# openx3_rev2.net
KiCad netlist of a schematic drawn in EAGLE
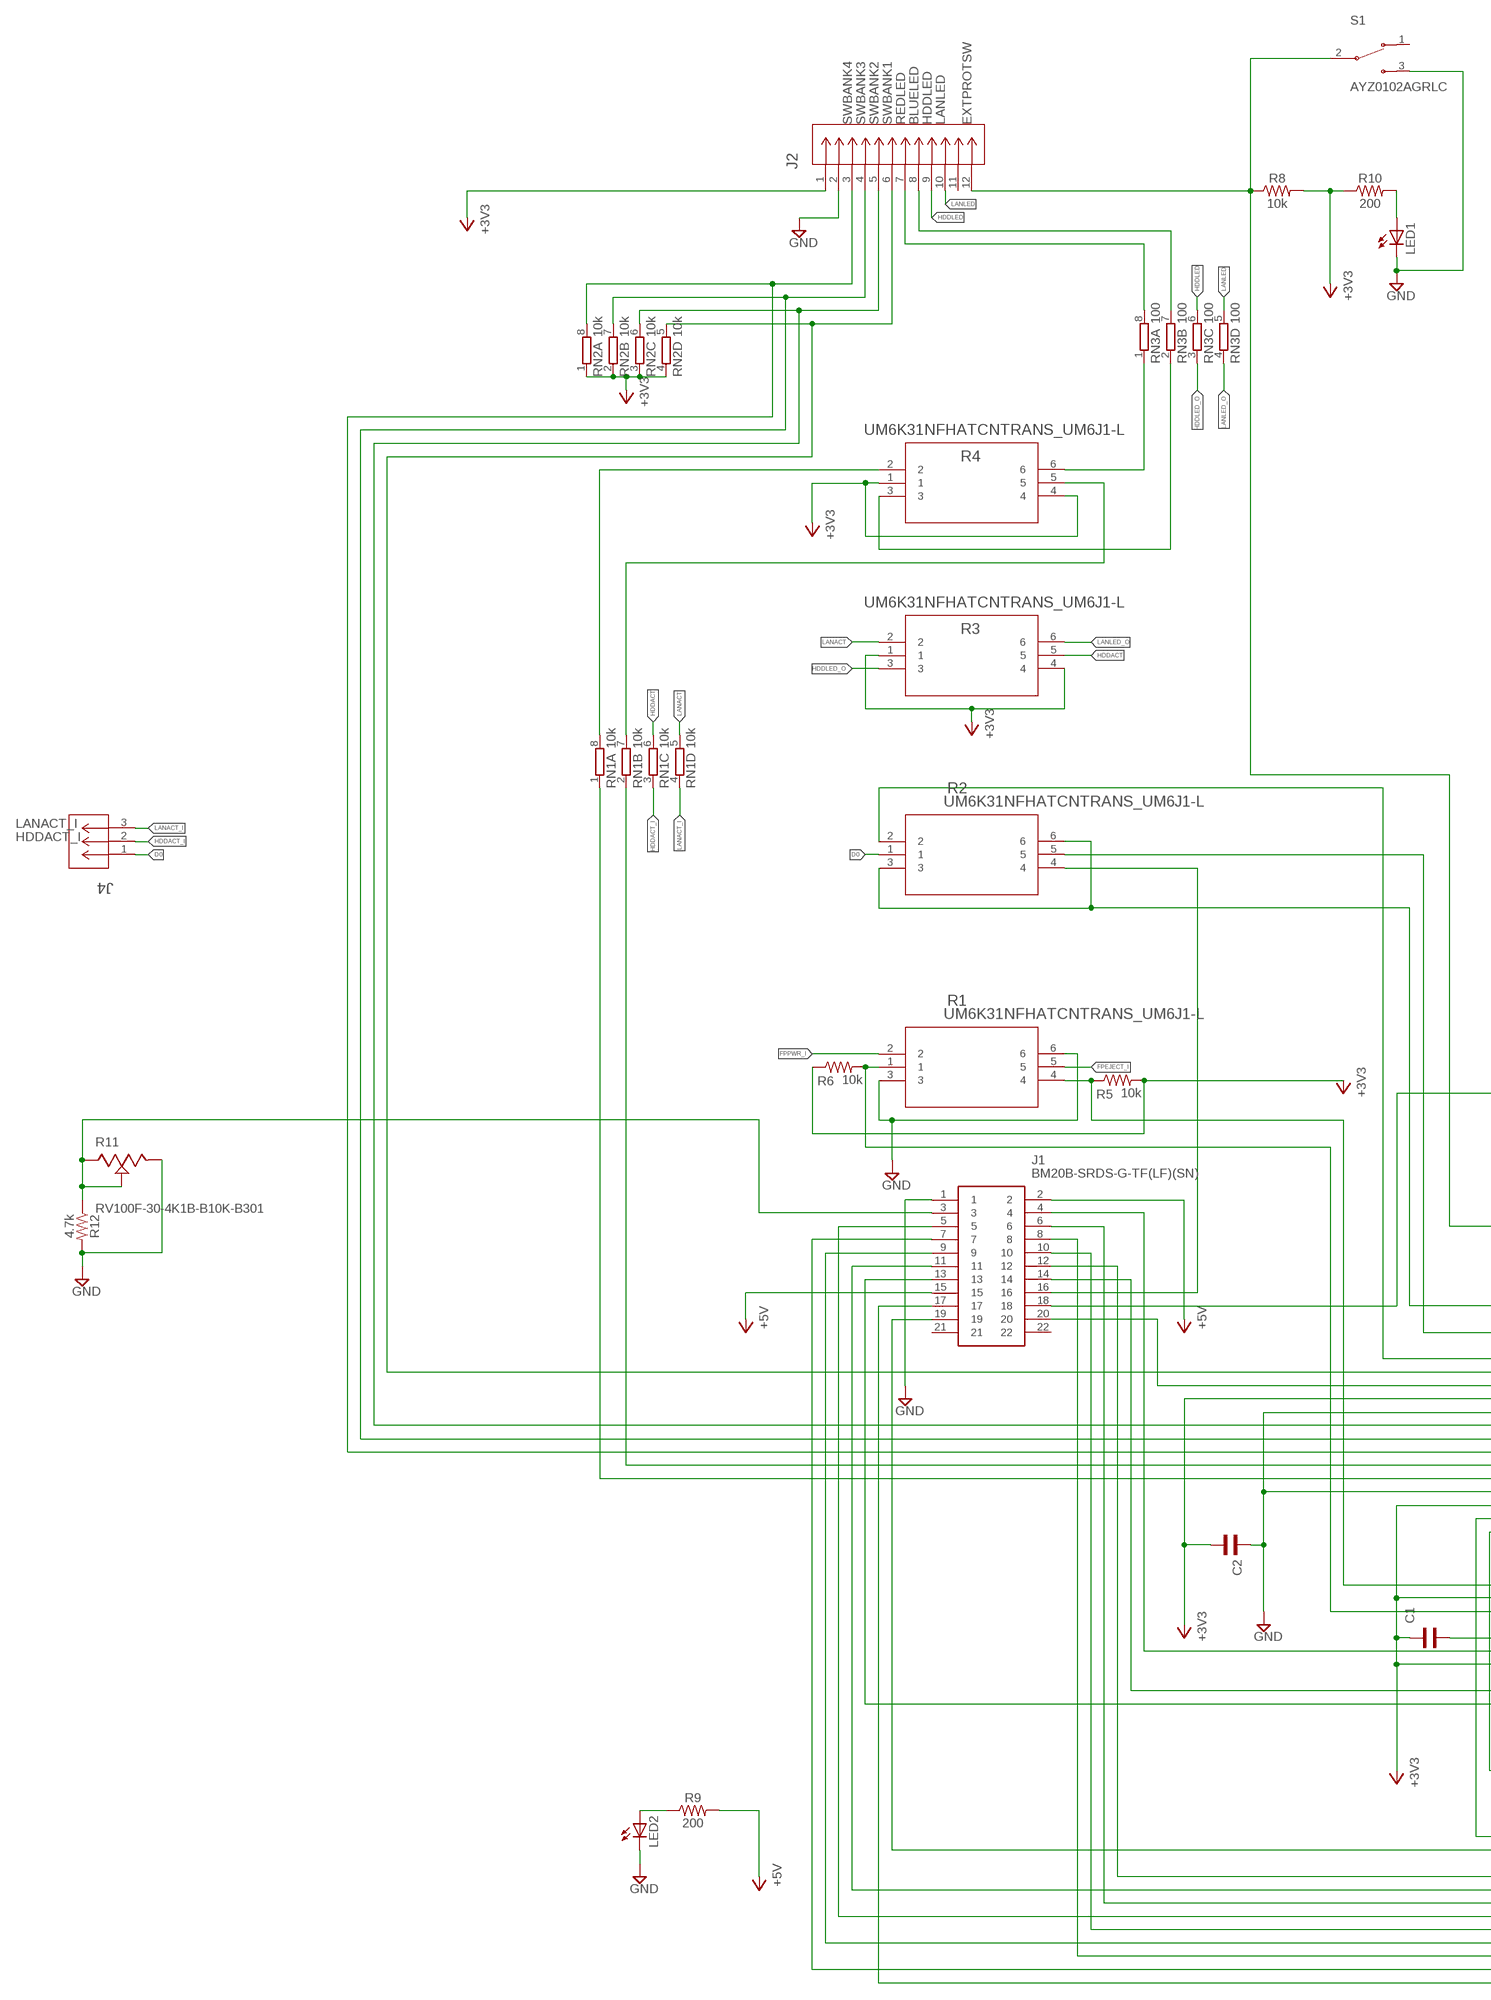
[diagram p0: schematic, sheet 1, part 1 of 2]
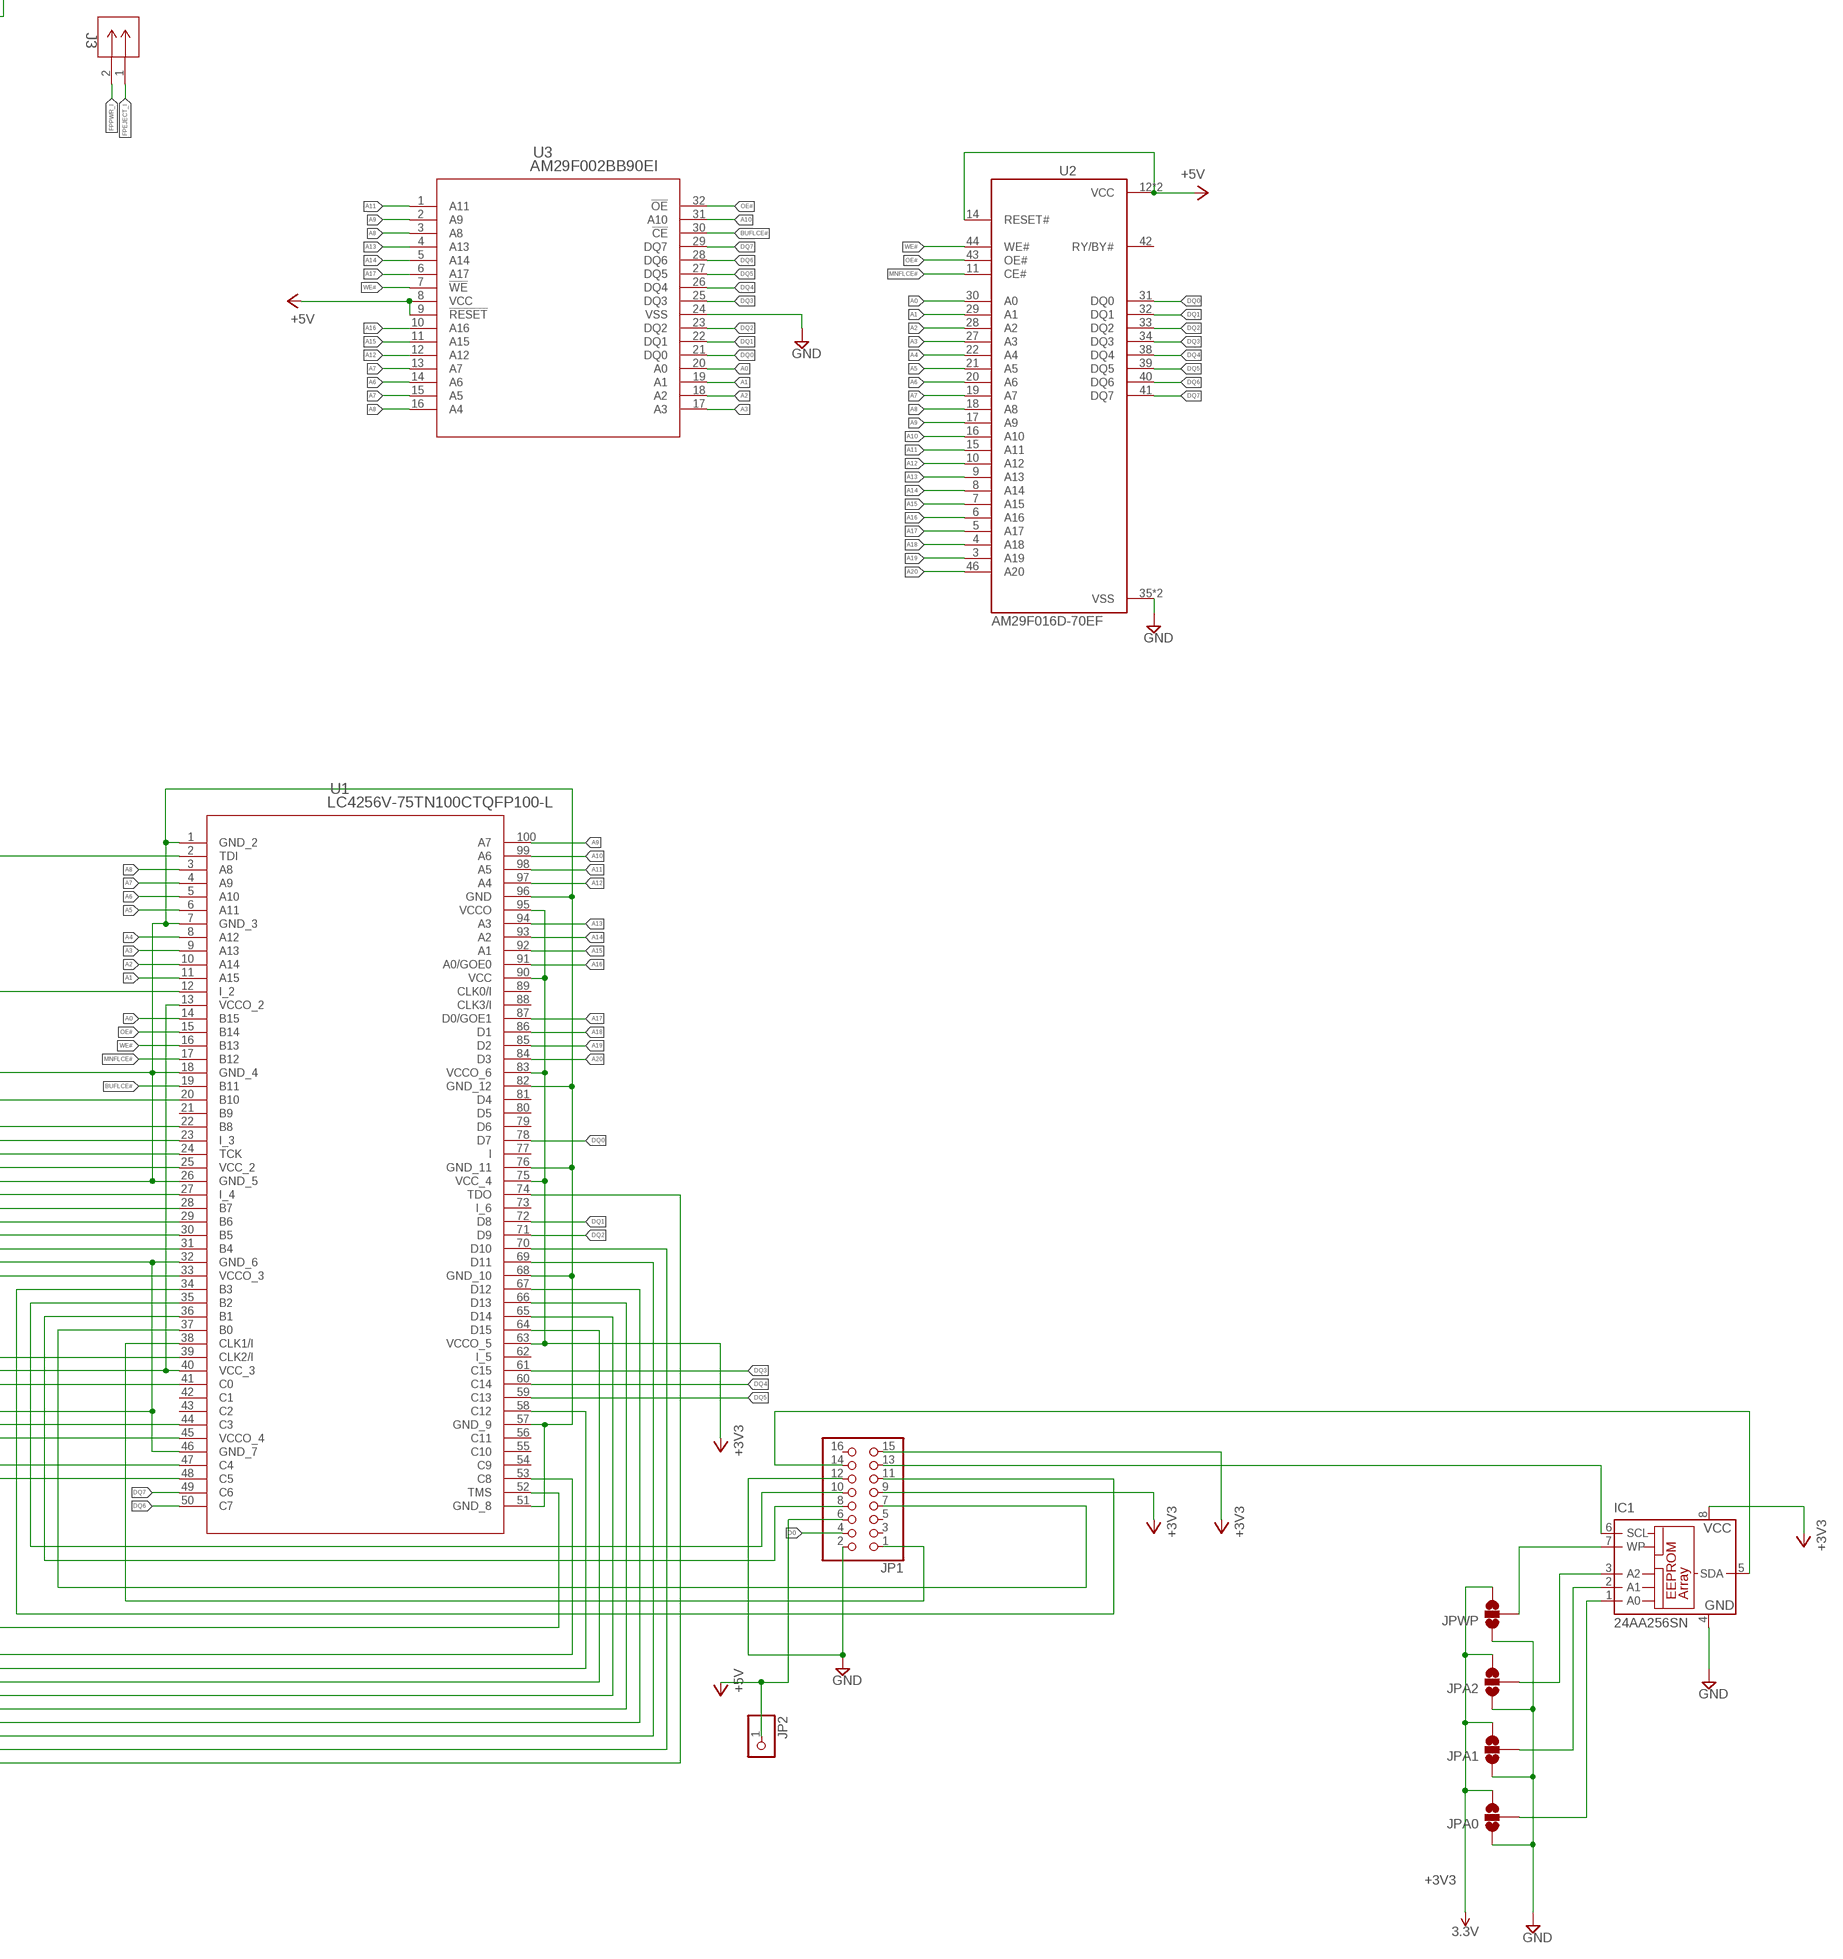
[diagram p1: schematic, sheet 1, part 2 of 2]

(export (version "E")
  (design (tool "Eeschema 10.0.6"))
  (components
    (comp (ref "C1")
      (value "WCAP-CSGP_0603_885012006001_REFLOW")
      (footprint "eagle-import:WCAP-CSGP_0603_REFLOW")
      (libsource (lib "eagle-import") (part "WCAP-CSGP_0603_REFLOW_885012006001"))
    )
    (comp (ref "C2")
      (value "WCAP-CSGP_0603_885012006001_REFLOW")
      (footprint "eagle-import:WCAP-CSGP_0603_REFLOW")
      (libsource (lib "eagle-import") (part "WCAP-CSGP_0603_REFLOW_885012006001"))
    )
    (comp (ref "IC1")
      (value "24AA256SN")
      (footprint "eagle-import:SO-08")
      (fields (field (name "MPN") "24AA256T-I/SM"))
      (libsource (lib "eagle-import") (part "24SNAA256"))
    )
    (comp (ref "J1")
      (value "BM20B-SRDS-G-TF(LF)(SN)")
      (footprint "eagle-import:BM20BSRDSGTFLFSN")
      (libsource (lib "eagle-import") (part "BM20B-SRDS-G-TF(LF)(SN)"))
    )
    (comp (ref "J2")
      (value "SM12B-SRSS-TB(LF)(SN)")
      (footprint "eagle-import:CONN_SM12B-SRSS-TB(LF)(SN)")
      (fields (field (name "COPYRIGHT") "Copyright (C) 2018 Accelerated Designs. All rights reserved"))
      (libsource (lib "eagle-import") (part "SM12B-SRSS-TB(LF)(SN)"))
    )
    (comp (ref "J3")
      (value "53398-0271")
      (footprint "eagle-import:CON00327_2")
      (fields (field (name "COPYRIGHT") "Copyright (C) 2016 Accelerated Designs. All rights reserved"))
      (libsource (lib "eagle-import") (part "53398-0271"))
    )
    (comp (ref "J4")
      (value "1734260-3")
      (footprint "eagle-import:CON3_1X3_DRM125_HPI")
      (libsource (lib "eagle-import") (part "1734260-3"))
    )
    (comp (ref "JP1")
      (value "PINHD-2X8")
      (footprint "eagle-import:2X08")
      (libsource (lib "eagle-import") (part "PINHD-2X8"))
    )
    (comp (ref "JP2")
      (value "PINHD-1X1")
      (footprint "eagle-import:1X01")
      (libsource (lib "eagle-import") (part "PINHD-1X1"))
    )
    (comp (ref "JPA0")
      (value "JUMPER-SMT_3_NO_NO-SILK")
      (footprint "eagle-import:SMT-JUMPER_3_NO_NO-SILK")
      (libsource (lib "eagle-import") (part "JUMPER-SMT_3_NO_NO-SILK"))
    )
    (comp (ref "JPA1")
      (value "JUMPER-SMT_3_NO_NO-SILK")
      (footprint "eagle-import:SMT-JUMPER_3_NO_NO-SILK")
      (libsource (lib "eagle-import") (part "JUMPER-SMT_3_NO_NO-SILK"))
    )
    (comp (ref "JPA2")
      (value "JUMPER-SMT_3_NO_NO-SILK")
      (footprint "eagle-import:SMT-JUMPER_3_NO_NO-SILK")
      (libsource (lib "eagle-import") (part "JUMPER-SMT_3_NO_NO-SILK"))
    )
    (comp (ref "JPWP")
      (value "JUMPER-SMT_3_NO_NO-SILK")
      (footprint "eagle-import:SMT-JUMPER_3_NO_NO-SILK")
      (libsource (lib "eagle-import") (part "JUMPER-SMT_3_NO_NO-SILK"))
    )
    (comp (ref "LED1")
      (value "LEDCHIPLED_0805")
      (footprint "eagle-import:CHIPLED_0805")
      (libsource (lib "eagle-import") (part "LEDCHIPLED_0805"))
    )
    (comp (ref "LED2")
      (value "LEDCHIPLED_0805")
      (footprint "eagle-import:CHIPLED_0805")
      (libsource (lib "eagle-import") (part "LEDCHIPLED_0805"))
    )
    (comp (ref "R1")
      (value "UM6K31NFHATCNTRANS_UM6J1-L")
      (footprint "eagle-import:TRANS_UM6J1-L")
      (fields
        (field (name "MANUFACTURER_PART_NUMBER") "UM6K31NFHATCN")
        (field (name "COPYRIGHT") "Copyright (C) 2018 Accelerated Designs. All rights reserved")
      )
      (libsource (lib "eagle-import") (part "UM6K31NFHATCNTRANS_UM6J1-L"))
    )
    (comp (ref "R2")
      (value "UM6K31NFHATCNTRANS_UM6J1-L")
      (footprint "eagle-import:TRANS_UM6J1-L")
      (fields
        (field (name "MANUFACTURER_PART_NUMBER") "UM6K31NFHATCN")
        (field (name "COPYRIGHT") "Copyright (C) 2018 Accelerated Designs. All rights reserved")
      )
      (libsource (lib "eagle-import") (part "UM6K31NFHATCNTRANS_UM6J1-L"))
    )
    (comp (ref "R3")
      (value "UM6K31NFHATCNTRANS_UM6J1-L")
      (footprint "eagle-import:TRANS_UM6J1-L")
      (fields
        (field (name "MANUFACTURER_PART_NUMBER") "UM6K31NFHATCN")
        (field (name "COPYRIGHT") "Copyright (C) 2018 Accelerated Designs. All rights reserved")
      )
      (libsource (lib "eagle-import") (part "UM6K31NFHATCNTRANS_UM6J1-L"))
    )
    (comp (ref "R4")
      (value "UM6K31NFHATCNTRANS_UM6J1-L")
      (footprint "eagle-import:TRANS_UM6J1-L")
      (fields
        (field (name "MANUFACTURER_PART_NUMBER") "UM6K31NFHATCN")
        (field (name "COPYRIGHT") "Copyright (C) 2018 Accelerated Designs. All rights reserved")
      )
      (libsource (lib "eagle-import") (part "UM6K31NFHATCNTRANS_UM6J1-L"))
    )
    (comp (ref "R5")
      (value "10k")
      (footprint "eagle-import:0603")
      (libsource (lib "eagle-import") (part "10KOHM-0603-1/10W-1%"))
    )
    (comp (ref "R6")
      (value "10k")
      (footprint "eagle-import:0603")
      (libsource (lib "eagle-import") (part "10KOHM-0603-1/10W-1%"))
    )
    (comp (ref "R8")
      (value "10k")
      (footprint "eagle-import:0603")
      (libsource (lib "eagle-import") (part "10KOHM-0603-1/10W-1%"))
    )
    (comp (ref "R9")
      (value "200")
      (footprint "eagle-import:0603")
      (libsource (lib "eagle-import") (part "200OHM-0603-1/10W-1%"))
    )
    (comp (ref "R10")
      (value "200")
      (footprint "eagle-import:0603")
      (libsource (lib "eagle-import") (part "200OHM-0603-1/10W-1%"))
    )
    (comp (ref "R11")
      (value "RV100F-30-4K1B-B10K-B301")
      (footprint "eagle-import:TRIM_RV100F-30-4K1B-B10K-B301")
      (fields (field (name "MF") "Alpha Taiwan"))
      (libsource (lib "eagle-import") (part "RV100F-30-4K1B-B10K-B301"))
    )
    (comp (ref "R12")
      (value "4.7k")
      (footprint "eagle-import:0603")
      (libsource (lib "eagle-import") (part "4.7KOHM-0603-1/10W-1%"))
    )
    (comp (ref "RN1")
      (value "10k")
      (footprint "eagle-import:0603-ARV")
      (libsource (lib "eagle-import") (part "4R-N0603-ARV"))
    )
    (comp (ref "RN2")
      (value "10k")
      (footprint "eagle-import:0603-ARV")
      (libsource (lib "eagle-import") (part "4R-N0603-ARV"))
    )
    (comp (ref "RN3")
      (value "100")
      (footprint "eagle-import:0603-ARV")
      (libsource (lib "eagle-import") (part "4R-N0603-ARV"))
    )
    (comp (ref "S1")
      (value "AYZ0102AGRLC")
      (footprint "eagle-import:SW_AYZ0102AGRLC")
      (fields (field (name "MF") "C&K"))
      (libsource (lib "eagle-import") (part "AYZ0102AGRLC"))
    )
    (comp (ref "U1")
      (value "LC4256V-75TN100CTQFP100-L")
      (footprint "eagle-import:TQFP100-L")
      (fields (field (name "MANUFACTURER_PART_NUMBER") "LC4256V-75TN100C"))
      (libsource (lib "eagle-import") (part "LC4256V-75TN100CTQFP100-L"))
    )
    (comp (ref "U2")
      (value "AM29F016D-70EF")
      (footprint "eagle-import:SOP50P2000X120-48N")
      (fields (field (name "MF") "Spansion"))
      (libsource (lib "eagle-import") (part "AM29F016D-70EF"))
    )
    (comp (ref "U3")
      (value "AM29F002BB90EI")
      (footprint "eagle-import:TS032")
      (libsource (lib "eagle-import") (part "AM29F002BB90EI"))
    )
  )
  (nets
    (net (code "1") (name "+3V3") (class "Default")
      (node (ref "C1") (pin "2") (pinfunction "2_2") (pintype "passive"))
      (node (ref "C2") (pin "1") (pinfunction "1_1") (pintype "passive"))
      (node (ref "IC1") (pin "8") (pinfunction "VCC_8") (pintype "power_in"))
      (node (ref "J2") (pin "1") (pinfunction "1_1") (pintype "passive"))
      (node (ref "JP1") (pin "15") (pinfunction "15_15") (pintype "passive"))
      (node (ref "JP1") (pin "9") (pinfunction "9_9") (pintype "passive"))
      (node (ref "JPA0") (pin "3") (pinfunction "3_3") (pintype "passive"))
      (node (ref "JPA1") (pin "3") (pinfunction "3_3") (pintype "passive"))
      (node (ref "JPA2") (pin "3") (pinfunction "3_3") (pintype "passive"))
      (node (ref "JPWP") (pin "3") (pinfunction "3_3") (pintype "passive"))
      (node (ref "R10") (pin "1") (pinfunction "1_1") (pintype "passive"))
      (node (ref "R3") (pin "1") (pinfunction "1_1") (pintype "passive"))
      (node (ref "R3") (pin "4") (pinfunction "4_4") (pintype "passive"))
      (node (ref "R4") (pin "1") (pinfunction "1_1") (pintype "passive"))
      (node (ref "R4") (pin "4") (pinfunction "4_4") (pintype "passive"))
      (node (ref "R5") (pin "2") (pinfunction "2_2") (pintype "passive"))
      (node (ref "R6") (pin "1") (pinfunction "1_1") (pintype "passive"))
      (node (ref "R8") (pin "2") (pinfunction "2_2") (pintype "passive"))
      (node (ref "RN2") (pin "1") (pinfunction "1_1") (pintype "passive"))
      (node (ref "RN2") (pin "2") (pinfunction "1_2") (pintype "passive"))
      (node (ref "RN2") (pin "3") (pinfunction "1_3") (pintype "passive"))
      (node (ref "RN2") (pin "4") (pinfunction "1_4") (pintype "passive"))
      (node (ref "U1") (pin "13") (pinfunction "VCCO_2_13") (pintype "power_in"))
      (node (ref "U1") (pin "25") (pinfunction "VCC_2_25") (pintype "power_in"))
      (node (ref "U1") (pin "33") (pinfunction "VCCO_3_33") (pintype "power_in"))
      (node (ref "U1") (pin "40") (pinfunction "VCC_3_40") (pintype "power_in"))
      (node (ref "U1") (pin "45") (pinfunction "VCCO_4_45") (pintype "power_in"))
      (node (ref "U1") (pin "63") (pinfunction "VCCO_5_63") (pintype "power_in"))
      (node (ref "U1") (pin "75") (pinfunction "VCC_4_75") (pintype "power_in"))
      (node (ref "U1") (pin "83") (pinfunction "VCCO_6_83") (pintype "power_in"))
      (node (ref "U1") (pin "90") (pinfunction "VCC_90") (pintype "power_in"))
      (node (ref "U1") (pin "95") (pinfunction "VCCO_95") (pintype "power_in"))
    )
    (net (code "2") (name "+5V") (class "Default")
      (node (ref "J1") (pin "15") (pinfunction "15_15") (pintype "bidirectional"))
      (node (ref "J1") (pin "2") (pinfunction "2_2") (pintype "bidirectional"))
      (node (ref "JP1") (pin "6") (pinfunction "6_6") (pintype "passive"))
      (node (ref "JP2") (pin "1") (pinfunction "1_1") (pintype "passive"))
      (node (ref "R9") (pin "2") (pinfunction "2_2") (pintype "passive"))
      (node (ref "U2") (pin "12") (pinfunction "VCC_12") (pintype "power_in"))
      (node (ref "U2") (pin "14") (pinfunction "RESET#_14") (pintype "input"))
      (node (ref "U2") (pin "37") (pinfunction "VCC_37") (pintype "power_in"))
      (node (ref "U3") (pin "8") (pinfunction "VCC_8") (pintype "power_in"))
      (node (ref "U3") (pin "9") (pinfunction "~{RESET}_9") (pintype "input"))
    )
    (net (code "3") (name "/BLUELED") (class "Default")
      (node (ref "J2") (pin "8") (pinfunction "8_8") (pintype "passive"))
      (node (ref "RN3") (pin "7") (pinfunction "2_7") (pintype "passive"))
    )
    (net (code "4") (name "/EXTPROTSW") (class "Default")
      (node (ref "J2") (pin "12") (pinfunction "12_12") (pintype "passive"))
      (node (ref "R8") (pin "1") (pinfunction "1_1") (pintype "passive"))
      (node (ref "S1") (pin "2") (pinfunction "2_2") (pintype "passive"))
      (node (ref "U1") (pin "12") (pinfunction "I_2_12") (pintype "passive"))
    )
    (net (code "5") (name "/REDLED") (class "Default")
      (node (ref "J2") (pin "7") (pinfunction "7_7") (pintype "passive"))
      (node (ref "RN3") (pin "8") (pinfunction "2_8") (pintype "passive"))
    )
    (net (code "6") (name "/SWBANK1") (class "Default")
      (node (ref "J2") (pin "6") (pinfunction "6_6") (pintype "passive"))
      (node (ref "RN2") (pin "5") (pinfunction "2_5") (pintype "passive"))
      (node (ref "U1") (pin "23") (pinfunction "I_3_23") (pintype "passive"))
    )
    (net (code "7") (name "/SWBANK2") (class "Default")
      (node (ref "J2") (pin "5") (pinfunction "5_5") (pintype "passive"))
      (node (ref "RN2") (pin "6") (pinfunction "2_6") (pintype "passive"))
      (node (ref "U1") (pin "27") (pinfunction "I_4_27") (pintype "passive"))
    )
    (net (code "8") (name "/SWBANK3") (class "Default")
      (node (ref "J2") (pin "4") (pinfunction "4_4") (pintype "passive"))
      (node (ref "RN2") (pin "7") (pinfunction "2_7") (pintype "passive"))
      (node (ref "U1") (pin "28") (pinfunction "B7_28") (pintype "passive"))
    )
    (net (code "9") (name "/SWBANK4") (class "Default")
      (node (ref "J2") (pin "3") (pinfunction "3_3") (pintype "passive"))
      (node (ref "RN2") (pin "8") (pinfunction "2_8") (pintype "passive"))
      (node (ref "U1") (pin "29") (pinfunction "B6_29") (pintype "passive"))
    )
    (net (code "10") (name "A0") (class "Default")
      (node (ref "U1") (pin "14") (pinfunction "B15_14") (pintype "passive"))
      (node (ref "U2") (pin "30") (pinfunction "A0_30") (pintype "input"))
      (node (ref "U3") (pin "20") (pinfunction "A0_20") (pintype "input"))
    )
    (net (code "11") (name "A1") (class "Default")
      (node (ref "U1") (pin "11") (pinfunction "A15_11") (pintype "passive"))
      (node (ref "U2") (pin "29") (pinfunction "A1_29") (pintype "input"))
      (node (ref "U3") (pin "19") (pinfunction "A1_19") (pintype "input"))
    )
    (net (code "12") (name "A2") (class "Default")
      (node (ref "U1") (pin "10") (pinfunction "A14_10") (pintype "passive"))
      (node (ref "U2") (pin "28") (pinfunction "A2_28") (pintype "input"))
      (node (ref "U3") (pin "18") (pinfunction "A2_18") (pintype "input"))
    )
    (net (code "13") (name "A3") (class "Default")
      (node (ref "U1") (pin "9") (pinfunction "A13_9") (pintype "passive"))
      (node (ref "U2") (pin "27") (pinfunction "A3_27") (pintype "input"))
      (node (ref "U3") (pin "17") (pinfunction "A3_17") (pintype "input"))
    )
    (net (code "14") (name "A4") (class "Default")
      (node (ref "U1") (pin "8") (pinfunction "A12_8") (pintype "passive"))
      (node (ref "U2") (pin "22") (pinfunction "A4_22") (pintype "input"))
    )
    (net (code "15") (name "A5") (class "Default")
      (node (ref "U1") (pin "6") (pinfunction "A11_6") (pintype "passive"))
      (node (ref "U2") (pin "21") (pinfunction "A5_21") (pintype "input"))
    )
    (net (code "16") (name "A6") (class "Default")
      (node (ref "U1") (pin "5") (pinfunction "A10_5") (pintype "passive"))
      (node (ref "U2") (pin "20") (pinfunction "A6_20") (pintype "input"))
      (node (ref "U3") (pin "14") (pinfunction "A6_14") (pintype "input"))
    )
    (net (code "17") (name "A7") (class "Default")
      (node (ref "U1") (pin "4") (pinfunction "A9_4") (pintype "passive"))
      (node (ref "U2") (pin "19") (pinfunction "A7_19") (pintype "input"))
      (node (ref "U3") (pin "13") (pinfunction "A7_13") (pintype "input"))
      (node (ref "U3") (pin "15") (pinfunction "A5_15") (pintype "input"))
    )
    (net (code "18") (name "A8") (class "Default")
      (node (ref "U1") (pin "3") (pinfunction "A8_3") (pintype "passive"))
      (node (ref "U2") (pin "18") (pinfunction "A8_18") (pintype "input"))
      (node (ref "U3") (pin "16") (pinfunction "A4_16") (pintype "input"))
      (node (ref "U3") (pin "3") (pinfunction "A8_3") (pintype "input"))
    )
    (net (code "19") (name "A9") (class "Default")
      (node (ref "U1") (pin "100") (pinfunction "A7_100") (pintype "passive"))
      (node (ref "U2") (pin "17") (pinfunction "A9_17") (pintype "input"))
      (node (ref "U3") (pin "2") (pinfunction "A9_2") (pintype "input"))
    )
    (net (code "20") (name "A10") (class "Default")
      (node (ref "U1") (pin "99") (pinfunction "A6_99") (pintype "passive"))
      (node (ref "U2") (pin "16") (pinfunction "A10_16") (pintype "input"))
      (node (ref "U3") (pin "31") (pinfunction "A10_31") (pintype "input"))
    )
    (net (code "21") (name "A11") (class "Default")
      (node (ref "U1") (pin "98") (pinfunction "A5_98") (pintype "passive"))
      (node (ref "U2") (pin "15") (pinfunction "A11_15") (pintype "input"))
      (node (ref "U3") (pin "1") (pinfunction "A11_1") (pintype "input"))
    )
    (net (code "22") (name "A12") (class "Default")
      (node (ref "U1") (pin "97") (pinfunction "A4_97") (pintype "passive"))
      (node (ref "U2") (pin "10") (pinfunction "A12_10") (pintype "input"))
      (node (ref "U3") (pin "12") (pinfunction "A12_12") (pintype "input"))
    )
    (net (code "23") (name "A13") (class "Default")
      (node (ref "U1") (pin "94") (pinfunction "A3_94") (pintype "passive"))
      (node (ref "U2") (pin "9") (pinfunction "A13_9") (pintype "input"))
      (node (ref "U3") (pin "4") (pinfunction "A13_4") (pintype "input"))
    )
    (net (code "24") (name "A14") (class "Default")
      (node (ref "U1") (pin "93") (pinfunction "A2_93") (pintype "passive"))
      (node (ref "U2") (pin "8") (pinfunction "A14_8") (pintype "input"))
      (node (ref "U3") (pin "5") (pinfunction "A14_5") (pintype "input"))
    )
    (net (code "25") (name "A15") (class "Default")
      (node (ref "U1") (pin "92") (pinfunction "A1_92") (pintype "passive"))
      (node (ref "U2") (pin "7") (pinfunction "A15_7") (pintype "input"))
      (node (ref "U3") (pin "11") (pinfunction "A15_11") (pintype "input"))
    )
    (net (code "26") (name "A16") (class "Default")
      (node (ref "U1") (pin "91") (pinfunction "A0/GOE0_91") (pintype "passive"))
      (node (ref "U2") (pin "6") (pinfunction "A16_6") (pintype "input"))
      (node (ref "U3") (pin "10") (pinfunction "A16_10") (pintype "input"))
    )
    (net (code "27") (name "A17") (class "Default")
      (node (ref "U1") (pin "87") (pinfunction "D0/GOE1_87") (pintype "passive"))
      (node (ref "U2") (pin "5") (pinfunction "A17_5") (pintype "input"))
      (node (ref "U3") (pin "6") (pinfunction "A17_6") (pintype "input"))
    )
    (net (code "28") (name "A18") (class "Default")
      (node (ref "U1") (pin "86") (pinfunction "D1_86") (pintype "passive"))
      (node (ref "U2") (pin "4") (pinfunction "A18_4") (pintype "input"))
    )
    (net (code "29") (name "A19") (class "Default")
      (node (ref "U1") (pin "85") (pinfunction "D2_85") (pintype "passive"))
      (node (ref "U2") (pin "3") (pinfunction "A19_3") (pintype "input"))
    )
    (net (code "30") (name "A20") (class "Default")
      (node (ref "U1") (pin "84") (pinfunction "D3_84") (pintype "passive"))
      (node (ref "U2") (pin "46") (pinfunction "A20_46") (pintype "input"))
    )
    (net (code "31") (name "BUFLCE#") (class "Default")
      (node (ref "U1") (pin "19") (pinfunction "B11_19") (pintype "passive"))
      (node (ref "U3") (pin "30") (pinfunction "~{CE}_30") (pintype "input"))
    )
    (net (code "32") (name "D0") (class "Default")
      (node (ref "J4") (pin "1") (pinfunction "1_1") (pintype "passive"))
      (node (ref "JP1") (pin "4") (pinfunction "4_4") (pintype "passive"))
      (node (ref "R2") (pin "1") (pinfunction "1_1") (pintype "passive"))
    )
    (net (code "33") (name "DQ0") (class "Default")
      (node (ref "U1") (pin "78") (pinfunction "D7_78") (pintype "passive"))
      (node (ref "U2") (pin "31") (pinfunction "DQ0_31") (pintype "bidirectional"))
      (node (ref "U3") (pin "21") (pinfunction "DQ0_21") (pintype "bidirectional"))
    )
    (net (code "34") (name "DQ1") (class "Default")
      (node (ref "U1") (pin "72") (pinfunction "D8_72") (pintype "passive"))
      (node (ref "U2") (pin "32") (pinfunction "DQ1_32") (pintype "bidirectional"))
      (node (ref "U3") (pin "22") (pinfunction "DQ1_22") (pintype "bidirectional"))
    )
    (net (code "35") (name "DQ2") (class "Default")
      (node (ref "U1") (pin "71") (pinfunction "D9_71") (pintype "passive"))
      (node (ref "U2") (pin "33") (pinfunction "DQ2_33") (pintype "bidirectional"))
      (node (ref "U3") (pin "23") (pinfunction "DQ2_23") (pintype "bidirectional"))
    )
    (net (code "36") (name "DQ3") (class "Default")
      (node (ref "U1") (pin "61") (pinfunction "C15_61") (pintype "passive"))
      (node (ref "U2") (pin "34") (pinfunction "DQ3_34") (pintype "bidirectional"))
      (node (ref "U3") (pin "25") (pinfunction "DQ3_25") (pintype "bidirectional"))
    )
    (net (code "37") (name "DQ4") (class "Default")
      (node (ref "U1") (pin "60") (pinfunction "C14_60") (pintype "passive"))
      (node (ref "U2") (pin "38") (pinfunction "DQ4_38") (pintype "bidirectional"))
      (node (ref "U3") (pin "26") (pinfunction "DQ4_26") (pintype "bidirectional"))
    )
    (net (code "38") (name "DQ5") (class "Default")
      (node (ref "U1") (pin "59") (pinfunction "C13_59") (pintype "passive"))
      (node (ref "U2") (pin "39") (pinfunction "DQ5_39") (pintype "bidirectional"))
      (node (ref "U3") (pin "27") (pinfunction "DQ5_27") (pintype "bidirectional"))
    )
    (net (code "39") (name "DQ6") (class "Default")
      (node (ref "U1") (pin "50") (pinfunction "C7_50") (pintype "passive"))
      (node (ref "U2") (pin "40") (pinfunction "DQ6_40") (pintype "bidirectional"))
      (node (ref "U3") (pin "28") (pinfunction "DQ6_28") (pintype "bidirectional"))
    )
    (net (code "40") (name "DQ7") (class "Default")
      (node (ref "U1") (pin "49") (pinfunction "C6_49") (pintype "passive"))
      (node (ref "U2") (pin "41") (pinfunction "DQ7_41") (pintype "bidirectional"))
      (node (ref "U3") (pin "29") (pinfunction "DQ7_29") (pintype "bidirectional"))
    )
    (net (code "41") (name "FPEJECT_I") (class "Default")
      (node (ref "J3") (pin "1") (pinfunction "1_1") (pintype "passive"))
      (node (ref "R1") (pin "5") (pinfunction "5_5") (pintype "passive"))
    )
    (net (code "42") (name "FPPWR_I") (class "Default")
      (node (ref "J3") (pin "2") (pinfunction "2_2") (pintype "passive"))
      (node (ref "R1") (pin "2") (pinfunction "2_2") (pintype "passive"))
    )
    (net (code "43") (name "GND") (class "Default")
      (node (ref "C1") (pin "1") (pinfunction "1_1") (pintype "passive"))
      (node (ref "C2") (pin "2") (pinfunction "2_2") (pintype "passive"))
      (node (ref "IC1") (pin "4") (pinfunction "GND_4") (pintype "power_in"))
      (node (ref "J1") (pin "1") (pinfunction "1_1") (pintype "bidirectional"))
      (node (ref "J2") (pin "2") (pinfunction "2_2") (pintype "passive"))
      (node (ref "JP1") (pin "12") (pinfunction "12_12") (pintype "passive"))
      (node (ref "JP1") (pin "2") (pinfunction "2_2") (pintype "passive"))
      (node (ref "JPA0") (pin "1") (pinfunction "1_1") (pintype "passive"))
      (node (ref "JPA1") (pin "1") (pinfunction "1_1") (pintype "passive"))
      (node (ref "JPA2") (pin "1") (pinfunction "1_1") (pintype "passive"))
      (node (ref "JPWP") (pin "1") (pinfunction "1_1") (pintype "passive"))
      (node (ref "LED1") (pin "C") (pinfunction "C_C") (pintype "passive"))
      (node (ref "LED2") (pin "C") (pinfunction "C_C") (pintype "passive"))
      (node (ref "R1") (pin "3") (pinfunction "3_3") (pintype "passive"))
      (node (ref "R1") (pin "6") (pinfunction "6_6") (pintype "passive"))
      (node (ref "R11") (pin "3") (pinfunction "3_3") (pintype "passive"))
      (node (ref "R12") (pin "2") (pinfunction "2_2") (pintype "passive"))
      (node (ref "R2") (pin "3") (pinfunction "3_3") (pintype "passive"))
      (node (ref "R2") (pin "6") (pinfunction "6_6") (pintype "passive"))
      (node (ref "S1") (pin "3") (pinfunction "3_3") (pintype "passive"))
      (node (ref "U1") (pin "1") (pinfunction "GND_2_1") (pintype "power_in"))
      (node (ref "U1") (pin "18") (pinfunction "GND_4_18") (pintype "power_in"))
      (node (ref "U1") (pin "26") (pinfunction "GND_5_26") (pintype "power_in"))
      (node (ref "U1") (pin "32") (pinfunction "GND_6_32") (pintype "power_in"))
      (node (ref "U1") (pin "46") (pinfunction "GND_7_46") (pintype "power_in"))
      (node (ref "U1") (pin "51") (pinfunction "GND_8_51") (pintype "power_in"))
      (node (ref "U1") (pin "57") (pinfunction "GND_9_57") (pintype "power_in"))
      (node (ref "U1") (pin "68") (pinfunction "GND_10_68") (pintype "power_in"))
      (node (ref "U1") (pin "7") (pinfunction "GND_3_7") (pintype "power_in"))
      (node (ref "U1") (pin "76") (pinfunction "GND_11_76") (pintype "power_in"))
      (node (ref "U1") (pin "82") (pinfunction "GND_12_82") (pintype "power_in"))
      (node (ref "U1") (pin "96") (pinfunction "GND_96") (pintype "power_in"))
      (node (ref "U2") (pin "35") (pinfunction "VSS_35") (pintype "power_in"))
      (node (ref "U2") (pin "36") (pinfunction "VSS_36") (pintype "power_in"))
      (node (ref "U3") (pin "24") (pinfunction "VSS_24") (pintype "power_in"))
    )
    (net (code "44") (name "HDDACT") (class "Default")
      (node (ref "R3") (pin "5") (pinfunction "5_5") (pintype "passive"))
      (node (ref "RN1") (pin "6") (pinfunction "2_6") (pintype "passive"))
    )
    (net (code "45") (name "HDDACT_I") (class "Default")
      (node (ref "J4") (pin "2") (pinfunction "2_2") (pintype "passive"))
      (node (ref "RN1") (pin "3") (pinfunction "1_3") (pintype "passive"))
    )
    (net (code "46") (name "HDDLED") (class "Default")
      (node (ref "J2") (pin "9") (pinfunction "9_9") (pintype "passive"))
      (node (ref "RN3") (pin "6") (pinfunction "2_6") (pintype "passive"))
    )
    (net (code "47") (name "HDDLED_O") (class "Default")
      (node (ref "R3") (pin "3") (pinfunction "3_3") (pintype "passive"))
      (node (ref "RN3") (pin "3") (pinfunction "1_3") (pintype "passive"))
    )
    (net (code "48") (name "LANACT") (class "Default")
      (node (ref "R3") (pin "2") (pinfunction "2_2") (pintype "passive"))
      (node (ref "RN1") (pin "5") (pinfunction "2_5") (pintype "passive"))
    )
    (net (code "49") (name "LANACT_I") (class "Default")
      (node (ref "J4") (pin "3") (pinfunction "3_3") (pintype "passive"))
      (node (ref "RN1") (pin "4") (pinfunction "1_4") (pintype "passive"))
    )
    (net (code "50") (name "LANLED") (class "Default")
      (node (ref "J2") (pin "10") (pinfunction "10_10") (pintype "passive"))
      (node (ref "RN3") (pin "5") (pinfunction "2_5") (pintype "passive"))
    )
    (net (code "51") (name "LANLED_O") (class "Default")
      (node (ref "R3") (pin "6") (pinfunction "6_6") (pintype "passive"))
      (node (ref "RN3") (pin "4") (pinfunction "1_4") (pintype "passive"))
    )
    (net (code "52") (name "MNFLCE#") (class "Default")
      (node (ref "U1") (pin "17") (pinfunction "B12_17") (pintype "passive"))
      (node (ref "U2") (pin "11") (pinfunction "CE#_11") (pintype "input"))
    )
    (net (code "53") (name "Net-(IC1-A0)") (class "Default")
      (node (ref "IC1") (pin "1") (pinfunction "A0_1") (pintype "input"))
      (node (ref "JPA0") (pin "2") (pinfunction "2_2") (pintype "passive"))
    )
    (net (code "54") (name "Net-(IC1-A1)") (class "Default")
      (node (ref "IC1") (pin "2") (pinfunction "A1_2") (pintype "input"))
      (node (ref "JPA1") (pin "2") (pinfunction "2_2") (pintype "passive"))
    )
    (net (code "55") (name "Net-(IC1-A2)") (class "Default")
      (node (ref "IC1") (pin "3") (pinfunction "A2_3") (pintype "input"))
      (node (ref "JPA2") (pin "2") (pinfunction "2_2") (pintype "passive"))
    )
    (net (code "56") (name "Net-(IC1-SCL)") (class "Default")
      (node (ref "IC1") (pin "6") (pinfunction "SCL_6") (pintype "input"))
      (node (ref "JP1") (pin "13") (pinfunction "13_13") (pintype "passive"))
    )
    (net (code "57") (name "Net-(IC1-SDA)") (class "Default")
      (node (ref "IC1") (pin "5") (pinfunction "SDA_5") (pintype "bidirectional"))
      (node (ref "JP1") (pin "14") (pinfunction "14_14") (pintype "passive"))
    )
    (net (code "58") (name "Net-(IC1-WP)") (class "Default")
      (node (ref "IC1") (pin "7") (pinfunction "WP_7") (pintype "input"))
      (node (ref "JPWP") (pin "2") (pinfunction "2_2") (pintype "passive"))
    )
    (net (code "59") (name "Net-(J1-Pad3)") (class "Default")
      (node (ref "J1") (pin "3") (pinfunction "3_3") (pintype "bidirectional"))
      (node (ref "R11") (pin "1") (pinfunction "1_1") (pintype "passive"))
      (node (ref "R11") (pin "2") (pinfunction "2_2") (pintype "passive"))
      (node (ref "R12") (pin "1") (pinfunction "1_1") (pintype "passive"))
    )
    (net (code "60") (name "Net-(J1-Pad16)") (class "Default")
      (node (ref "J1") (pin "16") (pinfunction "16_16") (pintype "bidirectional"))
      (node (ref "R2") (pin "4") (pinfunction "4_4") (pintype "passive"))
    )
    (net (code "61") (name "Net-(LED1-PadA)") (class "Default")
      (node (ref "LED1") (pin "A") (pinfunction "A_A") (pintype "passive"))
      (node (ref "R10") (pin "2") (pinfunction "2_2") (pintype "passive"))
    )
    (net (code "62") (name "Net-(LED2-PadA)") (class "Default")
      (node (ref "LED2") (pin "A") (pinfunction "A_A") (pintype "passive"))
      (node (ref "R9") (pin "1") (pinfunction "1_1") (pintype "passive"))
    )
    (net (code "63") (name "Net-(R4-Pad6)") (class "Default")
      (node (ref "R4") (pin "6") (pinfunction "6_6") (pintype "passive"))
      (node (ref "RN3") (pin "1") (pinfunction "1_1") (pintype "passive"))
    )
    (net (code "64") (name "Net-(RN1A-2)") (class "Default")
      (node (ref "R4") (pin "2") (pinfunction "2_2") (pintype "passive"))
      (node (ref "RN1") (pin "8") (pinfunction "2_8") (pintype "passive"))
    )
    (net (code "65") (name "Net-(RN1B-1)") (class "Default")
      (node (ref "RN1") (pin "2") (pinfunction "1_2") (pintype "passive"))
      (node (ref "U1") (pin "30") (pinfunction "B5_30") (pintype "passive"))
    )
    (net (code "66") (name "Net-(RN1B-2)") (class "Default")
      (node (ref "R4") (pin "5") (pinfunction "5_5") (pintype "passive"))
      (node (ref "RN1") (pin "7") (pinfunction "2_7") (pintype "passive"))
    )
    (net (code "67") (name "Net-(RN3B-1)") (class "Default")
      (node (ref "R4") (pin "3") (pinfunction "3_3") (pintype "passive"))
      (node (ref "RN3") (pin "2") (pinfunction "1_2") (pintype "passive"))
    )
    (net (code "68") (name "Net-(U1-B0)") (class "Default")
      (node (ref "JP1") (pin "7") (pinfunction "7_7") (pintype "passive"))
      (node (ref "U1") (pin "37") (pinfunction "B0_37") (pintype "passive"))
    )
    (net (code "69") (name "Net-(U1-B1)") (class "Default")
      (node (ref "JP1") (pin "8") (pinfunction "8_8") (pintype "passive"))
      (node (ref "U1") (pin "36") (pinfunction "B1_36") (pintype "passive"))
    )
    (net (code "70") (name "Net-(U1-B2)") (class "Default")
      (node (ref "JP1") (pin "10") (pinfunction "10_10") (pintype "passive"))
      (node (ref "U1") (pin "35") (pinfunction "B2_35") (pintype "passive"))
    )
    (net (code "71") (name "Net-(U1-B3)") (class "Default")
      (node (ref "JP1") (pin "11") (pinfunction "11_11") (pintype "passive"))
      (node (ref "U1") (pin "34") (pinfunction "B3_34") (pintype "passive"))
    )
    (net (code "72") (name "Net-(U1-B4)") (class "Default")
      (node (ref "RN1") (pin "1") (pinfunction "1_1") (pintype "passive"))
      (node (ref "U1") (pin "31") (pinfunction "B4_31") (pintype "passive"))
    )
    (net (code "73") (name "Net-(U1-B8)") (class "Default")
      (node (ref "R2") (pin "2") (pinfunction "2_2") (pintype "passive"))
      (node (ref "U1") (pin "22") (pinfunction "B8_22") (pintype "passive"))
    )
    (net (code "74") (name "Net-(U1-B10)") (class "Default")
      (node (ref "R2") (pin "5") (pinfunction "5_5") (pintype "passive"))
      (node (ref "U1") (pin "20") (pinfunction "B10_20") (pintype "passive"))
    )
    (net (code "75") (name "Net-(U1-C0)") (class "Default")
      (node (ref "R1") (pin "1") (pinfunction "1_1") (pintype "passive"))
      (node (ref "R6") (pin "2") (pinfunction "2_2") (pintype "passive"))
      (node (ref "U1") (pin "41") (pinfunction "C0_41") (pintype "passive"))
    )
    (net (code "76") (name "Net-(U1-C3)") (class "Default")
      (node (ref "J1") (pin "4") (pinfunction "4_4") (pintype "bidirectional"))
      (node (ref "U1") (pin "44") (pinfunction "C3_44") (pintype "passive"))
    )
    (net (code "77") (name "Net-(U1-C4)") (class "Default")
      (node (ref "J1") (pin "14") (pinfunction "14_14") (pintype "bidirectional"))
      (node (ref "U1") (pin "47") (pinfunction "C4_47") (pintype "passive"))
    )
    (net (code "78") (name "Net-(U1-C5)") (class "Default")
      (node (ref "J1") (pin "13") (pinfunction "13_13") (pintype "bidirectional"))
      (node (ref "U1") (pin "48") (pinfunction "C5_48") (pintype "passive"))
    )
    (net (code "79") (name "Net-(U1-C8)") (class "Default")
      (node (ref "J1") (pin "12") (pinfunction "12_12") (pintype "bidirectional"))
      (node (ref "U1") (pin "53") (pinfunction "C8_53") (pintype "passive"))
    )
    (net (code "80") (name "Net-(U1-C12)") (class "Default")
      (node (ref "J1") (pin "11") (pinfunction "11_11") (pintype "bidirectional"))
      (node (ref "U1") (pin "58") (pinfunction "C12_58") (pintype "passive"))
    )
    (net (code "81") (name "Net-(U1-CLK1{slash}I)") (class "Default")
      (node (ref "JP1") (pin "1") (pinfunction "1_1") (pintype "passive"))
      (node (ref "U1") (pin "38") (pinfunction "CLK1/I_38") (pintype "passive"))
    )
    (net (code "82") (name "Net-(U1-CLK2{slash}I)") (class "Default")
      (node (ref "R1") (pin "4") (pinfunction "4_4") (pintype "passive"))
      (node (ref "R5") (pin "1") (pinfunction "1_1") (pintype "passive"))
      (node (ref "U1") (pin "39") (pinfunction "CLK2/I_39") (pintype "passive"))
    )
    (net (code "83") (name "Net-(U1-D10)") (class "Default")
      (node (ref "J1") (pin "7") (pinfunction "7_7") (pintype "bidirectional"))
      (node (ref "U1") (pin "70") (pinfunction "D10_70") (pintype "passive"))
    )
    (net (code "84") (name "Net-(U1-D11)") (class "Default")
      (node (ref "J1") (pin "8") (pinfunction "8_8") (pintype "bidirectional"))
      (node (ref "U1") (pin "69") (pinfunction "D11_69") (pintype "passive"))
    )
    (net (code "85") (name "Net-(U1-D12)") (class "Default")
      (node (ref "J1") (pin "9") (pinfunction "9_9") (pintype "bidirectional"))
      (node (ref "U1") (pin "67") (pinfunction "D12_67") (pintype "passive"))
    )
    (net (code "86") (name "Net-(U1-D13)") (class "Default")
      (node (ref "J1") (pin "10") (pinfunction "10_10") (pintype "bidirectional"))
      (node (ref "U1") (pin "66") (pinfunction "D13_66") (pintype "passive"))
    )
    (net (code "87") (name "Net-(U1-D14)") (class "Default")
      (node (ref "J1") (pin "5") (pinfunction "5_5") (pintype "bidirectional"))
      (node (ref "U1") (pin "65") (pinfunction "D14_65") (pintype "passive"))
    )
    (net (code "88") (name "Net-(U1-D15)") (class "Default")
      (node (ref "J1") (pin "6") (pinfunction "6_6") (pintype "bidirectional"))
      (node (ref "U1") (pin "64") (pinfunction "D15_64") (pintype "passive"))
    )
    (net (code "89") (name "Net-(U1-TCK)") (class "Default")
      (node (ref "J1") (pin "20") (pinfunction "20_20") (pintype "bidirectional"))
      (node (ref "U1") (pin "24") (pinfunction "TCK_24") (pintype "passive"))
    )
    (net (code "90") (name "Net-(U1-TDI)") (class "Default")
      (node (ref "J1") (pin "18") (pinfunction "18_18") (pintype "bidirectional"))
      (node (ref "U1") (pin "2") (pinfunction "TDI_2") (pintype "passive"))
    )
    (net (code "91") (name "Net-(U1-TDO)") (class "Default")
      (node (ref "J1") (pin "17") (pinfunction "17_17") (pintype "bidirectional"))
      (node (ref "U1") (pin "74") (pinfunction "TDO_74") (pintype "passive"))
    )
    (net (code "92") (name "Net-(U1-TMS)") (class "Default")
      (node (ref "J1") (pin "19") (pinfunction "19_19") (pintype "bidirectional"))
      (node (ref "U1") (pin "52") (pinfunction "TMS_52") (pintype "passive"))
    )
    (net (code "93") (name "OE#") (class "Default")
      (node (ref "U1") (pin "15") (pinfunction "B14_15") (pintype "passive"))
      (node (ref "U2") (pin "43") (pinfunction "OE#_43") (pintype "input"))
      (node (ref "U3") (pin "32") (pinfunction "~{OE}_32") (pintype "input"))
    )
    (net (code "94") (name "WE#") (class "Default")
      (node (ref "U1") (pin "16") (pinfunction "B13_16") (pintype "passive"))
      (node (ref "U2") (pin "44") (pinfunction "WE#_44") (pintype "input"))
      (node (ref "U3") (pin "7") (pinfunction "~{WE}_7") (pintype "input"))
    )
    (net (code "95") (name "unconnected-(J1-Pad21)") (class "Default")
      (node (ref "J1") (pin "21") (pinfunction "21_21") (pintype "bidirectional"))
    )
    (net (code "96") (name "unconnected-(J1-Pad22)") (class "Default")
      (node (ref "J1") (pin "22") (pinfunction "22_22") (pintype "bidirectional"))
    )
    (net (code "97") (name "unconnected-(J2-Pad11)") (class "Default")
      (node (ref "J2") (pin "11") (pinfunction "11_11") (pintype "passive"))
    )
    (net (code "98") (name "unconnected-(JP1-Pad3)") (class "Default")
      (node (ref "JP1") (pin "3") (pinfunction "3_3") (pintype "passive"))
    )
    (net (code "99") (name "unconnected-(JP1-Pad5)") (class "Default")
      (node (ref "JP1") (pin "5") (pinfunction "5_5") (pintype "passive"))
    )
    (net (code "100") (name "unconnected-(JP1-Pad16)") (class "Default")
      (node (ref "JP1") (pin "16") (pinfunction "16_16") (pintype "passive"))
    )
    (net (code "101") (name "unconnected-(S1-Pad1)") (class "Default")
      (node (ref "S1") (pin "1") (pinfunction "1_1") (pintype "passive"))
    )
    (net (code "102") (name "unconnected-(U1-B9-Pad21)") (class "Default")
      (node (ref "U1") (pin "21") (pinfunction "B9_21") (pintype "passive"))
    )
    (net (code "103") (name "unconnected-(U1-C1-Pad42)") (class "Default")
      (node (ref "U1") (pin "42") (pinfunction "C1_42") (pintype "passive"))
    )
    (net (code "104") (name "unconnected-(U1-C2-Pad43)") (class "Default")
      (node (ref "U1") (pin "43") (pinfunction "C2_43") (pintype "passive"))
    )
    (net (code "105") (name "unconnected-(U1-C9-Pad54)") (class "Default")
      (node (ref "U1") (pin "54") (pinfunction "C9_54") (pintype "passive"))
    )
    (net (code "106") (name "unconnected-(U1-C10-Pad55)") (class "Default")
      (node (ref "U1") (pin "55") (pinfunction "C10_55") (pintype "passive"))
    )
    (net (code "107") (name "unconnected-(U1-C11-Pad56)") (class "Default")
      (node (ref "U1") (pin "56") (pinfunction "C11_56") (pintype "passive"))
    )
    (net (code "108") (name "unconnected-(U1-CLK0{slash}I-Pad89)") (class "Default")
      (node (ref "U1") (pin "89") (pinfunction "CLK0/I_89") (pintype "passive"))
    )
    (net (code "109") (name "unconnected-(U1-CLK3{slash}I-Pad88)") (class "Default")
      (node (ref "U1") (pin "88") (pinfunction "CLK3/I_88") (pintype "passive"))
    )
    (net (code "110") (name "unconnected-(U1-D4-Pad81)") (class "Default")
      (node (ref "U1") (pin "81") (pinfunction "D4_81") (pintype "passive"))
    )
    (net (code "111") (name "unconnected-(U1-D5-Pad80)") (class "Default")
      (node (ref "U1") (pin "80") (pinfunction "D5_80") (pintype "passive"))
    )
    (net (code "112") (name "unconnected-(U1-D6-Pad79)") (class "Default")
      (node (ref "U1") (pin "79") (pinfunction "D6_79") (pintype "passive"))
    )
    (net (code "113") (name "unconnected-(U1-I-Pad77)") (class "Default")
      (node (ref "U1") (pin "77") (pinfunction "I_77") (pintype "passive"))
    )
    (net (code "114") (name "unconnected-(U1-I_5-Pad62)") (class "Default")
      (node (ref "U1") (pin "62") (pinfunction "I_5_62") (pintype "passive"))
    )
    (net (code "115") (name "unconnected-(U1-I_6-Pad73)") (class "Default")
      (node (ref "U1") (pin "73") (pinfunction "I_6_73") (pintype "passive"))
    )
    (net (code "116") (name "unconnected-(U2-RY{slash}BY#-Pad42)") (class "Default")
      (node (ref "U2") (pin "42") (pinfunction "RY/BY#_42") (pintype "output"))
    )
  )
)
